# nChannel.net
KiCad netlist of a schematic drawn in EAGLE
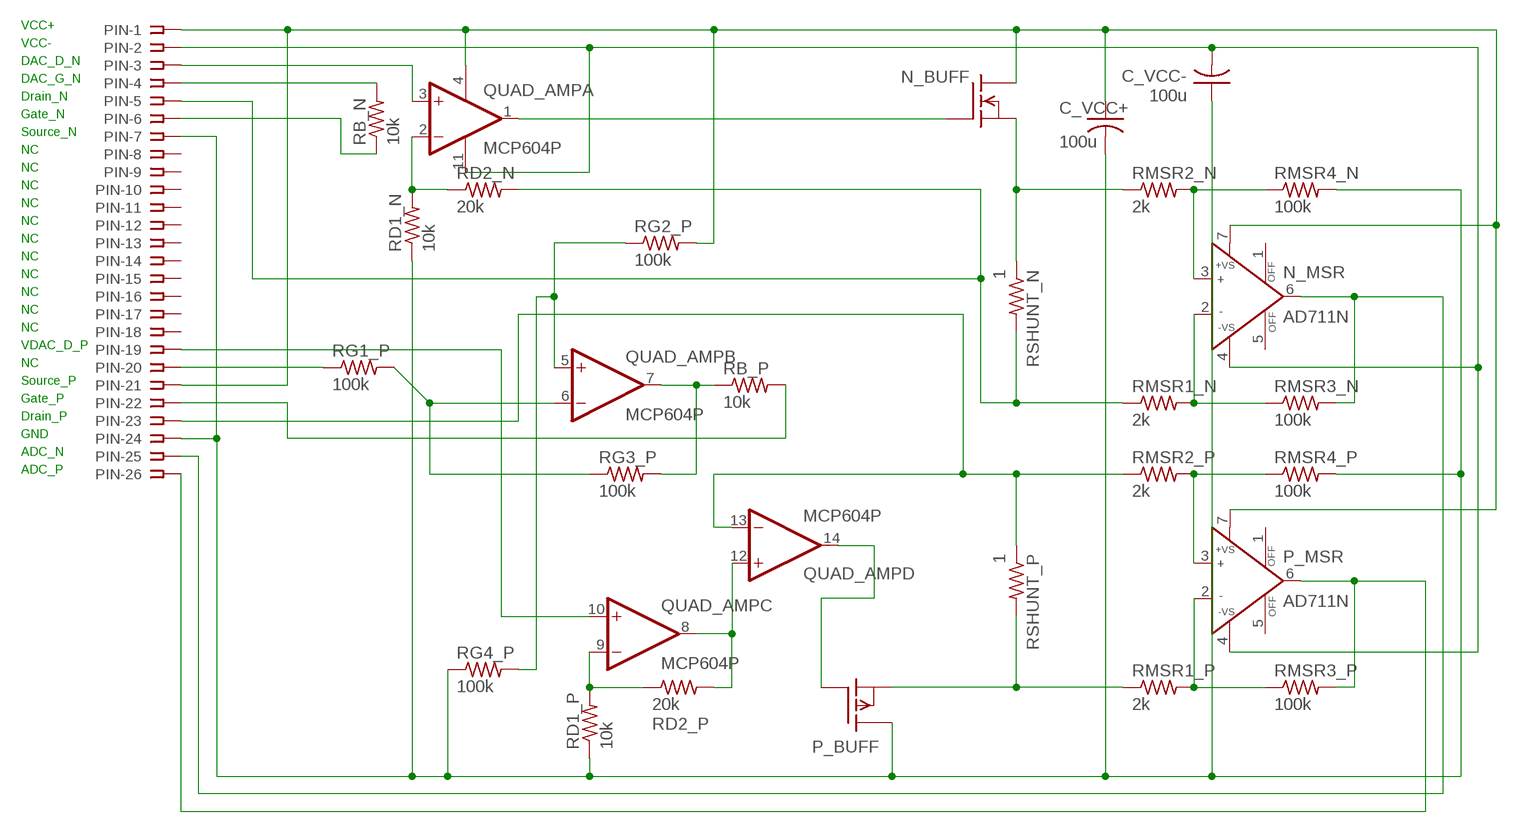
[diagram p0: schematic, sheet 1]

(export (version "E")
  (design (tool "Eeschema 10.0.6"))
  (components
    (comp (ref "C_VCC+")
      (value "100u")
      (footprint "eagle-import:C025-024X044")
      (libsource (lib "eagle-import") (part "C-US025-024X044"))
    )
    (comp (ref "C_VCC-")
      (value "100u")
      (footprint "eagle-import:C025-024X044")
      (libsource (lib "eagle-import") (part "C-US025-024X044"))
    )
    (comp (ref "N_BUFF")
      (value "BSS101")
      (footprint "eagle-import:TO92")
      (libsource (lib "eagle-import") (part "BSS101"))
    )
    (comp (ref "N_MSR")
      (value "AD711N")
      (footprint "eagle-import:DIL08")
      (fields (field (name "MPN") "AD711BQ"))
      (libsource (lib "eagle-import") (part "AD711N"))
    )
    (comp (ref "PIN")
      (value "SSW-126-02-G-S")
      (footprint "eagle-import:SSW-126-02-G-S")
      (fields (field (name "MF") "Samtec Inc."))
      (libsource (lib "eagle-import") (part "SSW-126-02-G-S"))
    )
    (comp (ref "P_BUFF")
      (value "BSS110")
      (footprint "eagle-import:TO92")
      (libsource (lib "eagle-import") (part "BSS110"))
    )
    (comp (ref "P_MSR")
      (value "AD711N")
      (footprint "eagle-import:DIL08")
      (fields (field (name "MPN") "AD711BQ"))
      (libsource (lib "eagle-import") (part "AD711N"))
    )
    (comp (ref "QUAD_AMP")
      (value "MCP604P")
      (footprint "eagle-import:DIL14")
      (libsource (lib "eagle-import") (part "MCP604P"))
    )
    (comp (ref "RB_N")
      (value "10k")
      (footprint "eagle-import:0204_5")
      (libsource (lib "eagle-import") (part "R-US_0204/5"))
    )
    (comp (ref "RB_P")
      (value "10k")
      (footprint "eagle-import:0204_5")
      (libsource (lib "eagle-import") (part "R-US_0204/5"))
    )
    (comp (ref "RD1_N")
      (value "10k")
      (footprint "eagle-import:0204_5")
      (libsource (lib "eagle-import") (part "R-US_0204/5"))
    )
    (comp (ref "RD1_P")
      (value "10k")
      (footprint "eagle-import:0204_5")
      (libsource (lib "eagle-import") (part "R-US_0204/5"))
    )
    (comp (ref "RD2_N")
      (value "20k")
      (footprint "eagle-import:0204_5")
      (libsource (lib "eagle-import") (part "R-US_0204/5"))
    )
    (comp (ref "RD2_P")
      (value "20k")
      (footprint "eagle-import:0204_5")
      (libsource (lib "eagle-import") (part "R-US_0204/5"))
    )
    (comp (ref "RG1_P")
      (value "100k")
      (footprint "eagle-import:0204_5")
      (libsource (lib "eagle-import") (part "R-US_0204/5"))
    )
    (comp (ref "RG2_P")
      (value "100k")
      (footprint "eagle-import:0204_5")
      (libsource (lib "eagle-import") (part "R-US_0204/5"))
    )
    (comp (ref "RG3_P")
      (value "100k")
      (footprint "eagle-import:0204_5")
      (libsource (lib "eagle-import") (part "R-US_0204/5"))
    )
    (comp (ref "RG4_P")
      (value "100k")
      (footprint "eagle-import:0204_5")
      (libsource (lib "eagle-import") (part "R-US_0204/5"))
    )
    (comp (ref "RMSR1_N")
      (value "2k")
      (footprint "eagle-import:0204_5")
      (libsource (lib "eagle-import") (part "R-US_0204/5"))
    )
    (comp (ref "RMSR1_P")
      (value "2k")
      (footprint "eagle-import:0204_5")
      (libsource (lib "eagle-import") (part "R-US_0204/5"))
    )
    (comp (ref "RMSR2_N")
      (value "2k")
      (footprint "eagle-import:0204_5")
      (libsource (lib "eagle-import") (part "R-US_0204/5"))
    )
    (comp (ref "RMSR2_P")
      (value "2k")
      (footprint "eagle-import:0204_5")
      (libsource (lib "eagle-import") (part "R-US_0204/5"))
    )
    (comp (ref "RMSR3_N")
      (value "100k")
      (footprint "eagle-import:0204_5")
      (libsource (lib "eagle-import") (part "R-US_0204/5"))
    )
    (comp (ref "RMSR3_P")
      (value "100k")
      (footprint "eagle-import:0204_5")
      (libsource (lib "eagle-import") (part "R-US_0204/5"))
    )
    (comp (ref "RMSR4_N")
      (value "100k")
      (footprint "eagle-import:0204_5")
      (libsource (lib "eagle-import") (part "R-US_0204/5"))
    )
    (comp (ref "RMSR4_P")
      (value "100k")
      (footprint "eagle-import:0204_5")
      (libsource (lib "eagle-import") (part "R-US_0204/5"))
    )
    (comp (ref "RSHUNT_N")
      (value "1")
      (footprint "eagle-import:0204_5")
      (fields (field (name "SPICEPREFIX") "52"))
      (libsource (lib "eagle-import") (part "R-US_0204/5"))
    )
    (comp (ref "RSHUNT_P")
      (value "1")
      (footprint "eagle-import:0204_5")
      (fields (field (name "SPICEPREFIX") "52"))
      (libsource (lib "eagle-import") (part "R-US_0204/5"))
    )
  )
  (nets
    (net (code "1") (name "Net-(N_BUFF-D)") (class "Default")
      (node (ref "C_VCC+") (pin "1") (pinfunction "1_1") (pintype "passive"))
      (node (ref "N_BUFF") (pin "3") (pinfunction "D_3") (pintype "passive"))
      (node (ref "N_MSR") (pin "7") (pinfunction "+VS_7") (pintype "input"))
      (node (ref "PIN") (pin "1") (pinfunction "1_1") (pintype "passive"))
      (node (ref "PIN") (pin "21") (pinfunction "1_21") (pintype "passive"))
      (node (ref "P_MSR") (pin "7") (pinfunction "+VS_7") (pintype "input"))
      (node (ref "QUAD_AMP") (pin "4") (pinfunction "V+_4") (pintype "power_in"))
      (node (ref "RG2_P") (pin "2") (pinfunction "2_2") (pintype "passive"))
    )
    (net (code "2") (name "Net-(N_BUFF-G)") (class "Default")
      (node (ref "N_BUFF") (pin "2") (pinfunction "G_2") (pintype "passive"))
      (node (ref "QUAD_AMP") (pin "1") (pinfunction "OUT_1") (pintype "output"))
    )
    (net (code "3") (name "Net-(N_BUFF-S)") (class "Default")
      (node (ref "N_BUFF") (pin "1") (pinfunction "S_1") (pintype "passive"))
      (node (ref "RMSR2_N") (pin "1") (pinfunction "1_1") (pintype "passive"))
      (node (ref "RSHUNT_N") (pin "1") (pinfunction "1_1") (pintype "passive"))
    )
    (net (code "4") (name "Net-(N_MSR--VS)") (class "Default")
      (node (ref "C_VCC-") (pin "2") (pinfunction "2_2") (pintype "passive"))
      (node (ref "N_MSR") (pin "4") (pinfunction "-VS_4") (pintype "input"))
      (node (ref "PIN") (pin "2") (pinfunction "1_2") (pintype "passive"))
      (node (ref "P_MSR") (pin "4") (pinfunction "-VS_4") (pintype "input"))
      (node (ref "QUAD_AMP") (pin "11") (pinfunction "V-_11") (pintype "power_in"))
    )
    (net (code "5") (name "Net-(N_MSR-IN+)") (class "Default")
      (node (ref "N_MSR") (pin "3") (pinfunction "IN+_3") (pintype "input"))
      (node (ref "RMSR2_N") (pin "2") (pinfunction "2_2") (pintype "passive"))
      (node (ref "RMSR4_N") (pin "1") (pinfunction "1_1") (pintype "passive"))
    )
    (net (code "6") (name "Net-(N_MSR-IN-)") (class "Default")
      (node (ref "N_MSR") (pin "2") (pinfunction "IN-_2") (pintype "input"))
      (node (ref "RMSR1_N") (pin "2") (pinfunction "2_2") (pintype "passive"))
      (node (ref "RMSR3_N") (pin "1") (pinfunction "1_1") (pintype "passive"))
    )
    (net (code "7") (name "Net-(N_MSR-OUT)") (class "Default")
      (node (ref "N_MSR") (pin "6") (pinfunction "OUT_6") (pintype "output"))
      (node (ref "PIN") (pin "25") (pinfunction "1_25") (pintype "passive"))
      (node (ref "RMSR3_N") (pin "2") (pinfunction "2_2") (pintype "passive"))
    )
    (net (code "8") (name "Net-(PINK-1)") (class "Default")
      (node (ref "PIN") (pin "19") (pinfunction "1_19") (pintype "passive"))
      (node (ref "QUAD_AMP") (pin "10") (pinfunction "+IN_10") (pintype "input"))
    )
    (net (code "9") (name "Net-(PINM-1)") (class "Default")
      (node (ref "PIN") (pin "20") (pinfunction "1_20") (pintype "passive"))
      (node (ref "RG1_P") (pin "1") (pinfunction "1_1") (pintype "passive"))
    )
    (net (code "10") (name "Net-(PINO-1)") (class "Default")
      (node (ref "PIN") (pin "22") (pinfunction "1_22") (pintype "passive"))
      (node (ref "RB_P") (pin "2") (pinfunction "2_2") (pintype "passive"))
    )
    (net (code "11") (name "Net-(PINP-1)") (class "Default")
      (node (ref "PIN") (pin "23") (pinfunction "1_23") (pintype "passive"))
      (node (ref "QUAD_AMP") (pin "13") (pinfunction "-IN_13") (pintype "input"))
      (node (ref "RMSR2_P") (pin "1") (pinfunction "1_1") (pintype "passive"))
      (node (ref "RSHUNT_P") (pin "1") (pinfunction "1_1") (pintype "passive"))
    )
    (net (code "12") (name "Net-(PINQ-1)") (class "Default")
      (node (ref "C_VCC+") (pin "2") (pinfunction "2_2") (pintype "passive"))
      (node (ref "C_VCC-") (pin "1") (pinfunction "1_1") (pintype "passive"))
      (node (ref "PIN") (pin "24") (pinfunction "1_24") (pintype "passive"))
      (node (ref "PIN") (pin "7") (pinfunction "1_7") (pintype "passive"))
      (node (ref "P_BUFF") (pin "3") (pinfunction "D_3") (pintype "passive"))
      (node (ref "RD1_N") (pin "1") (pinfunction "1_1") (pintype "passive"))
      (node (ref "RD1_P") (pin "1") (pinfunction "1_1") (pintype "passive"))
      (node (ref "RG4_P") (pin "1") (pinfunction "1_1") (pintype "passive"))
      (node (ref "RMSR4_N") (pin "2") (pinfunction "2_2") (pintype "passive"))
      (node (ref "RMSR4_P") (pin "2") (pinfunction "2_2") (pintype "passive"))
    )
    (net (code "13") (name "Net-(PINS-1)") (class "Default")
      (node (ref "PIN") (pin "26") (pinfunction "1_26") (pintype "passive"))
      (node (ref "P_MSR") (pin "6") (pinfunction "OUT_6") (pintype "output"))
      (node (ref "RMSR3_P") (pin "2") (pinfunction "2_2") (pintype "passive"))
    )
    (net (code "14") (name "Net-(PINT-1)") (class "Default")
      (node (ref "PIN") (pin "3") (pinfunction "1_3") (pintype "passive"))
      (node (ref "QUAD_AMP") (pin "3") (pinfunction "+IN_3") (pintype "input"))
    )
    (net (code "15") (name "Net-(PINU-1)") (class "Default")
      (node (ref "PIN") (pin "4") (pinfunction "1_4") (pintype "passive"))
      (node (ref "RB_N") (pin "2") (pinfunction "2_2") (pintype "passive"))
    )
    (net (code "16") (name "Net-(PINV-1)") (class "Default")
      (node (ref "PIN") (pin "5") (pinfunction "1_5") (pintype "passive"))
      (node (ref "RD2_N") (pin "2") (pinfunction "2_2") (pintype "passive"))
      (node (ref "RMSR1_N") (pin "1") (pinfunction "1_1") (pintype "passive"))
      (node (ref "RSHUNT_N") (pin "2") (pinfunction "2_2") (pintype "passive"))
    )
    (net (code "17") (name "Net-(PINW-1)") (class "Default")
      (node (ref "PIN") (pin "6") (pinfunction "1_6") (pintype "passive"))
      (node (ref "RB_N") (pin "1") (pinfunction "1_1") (pintype "passive"))
    )
    (net (code "18") (name "Net-(P_BUFF-G)") (class "Default")
      (node (ref "P_BUFF") (pin "2") (pinfunction "G_2") (pintype "passive"))
      (node (ref "QUAD_AMP") (pin "14") (pinfunction "OUT_14") (pintype "output"))
    )
    (net (code "19") (name "Net-(P_BUFF-S)") (class "Default")
      (node (ref "P_BUFF") (pin "1") (pinfunction "S_1") (pintype "passive"))
      (node (ref "RMSR1_P") (pin "1") (pinfunction "1_1") (pintype "passive"))
      (node (ref "RSHUNT_P") (pin "2") (pinfunction "2_2") (pintype "passive"))
    )
    (net (code "20") (name "Net-(P_MSR-IN+)") (class "Default")
      (node (ref "P_MSR") (pin "3") (pinfunction "IN+_3") (pintype "input"))
      (node (ref "RMSR2_P") (pin "2") (pinfunction "2_2") (pintype "passive"))
      (node (ref "RMSR4_P") (pin "1") (pinfunction "1_1") (pintype "passive"))
    )
    (net (code "21") (name "Net-(P_MSR-IN-)") (class "Default")
      (node (ref "P_MSR") (pin "2") (pinfunction "IN-_2") (pintype "input"))
      (node (ref "RMSR1_P") (pin "2") (pinfunction "2_2") (pintype "passive"))
      (node (ref "RMSR3_P") (pin "1") (pinfunction "1_1") (pintype "passive"))
    )
    (net (code "22") (name "Net-(QUAD_AMPA--IN)") (class "Default")
      (node (ref "QUAD_AMP") (pin "2") (pinfunction "-IN_2") (pintype "input"))
      (node (ref "RD1_N") (pin "2") (pinfunction "2_2") (pintype "passive"))
      (node (ref "RD2_N") (pin "1") (pinfunction "1_1") (pintype "passive"))
    )
    (net (code "23") (name "Net-(QUAD_AMPB-+IN)") (class "Default")
      (node (ref "QUAD_AMP") (pin "5") (pinfunction "+IN_5") (pintype "input"))
      (node (ref "RG2_P") (pin "1") (pinfunction "1_1") (pintype "passive"))
      (node (ref "RG4_P") (pin "2") (pinfunction "2_2") (pintype "passive"))
    )
    (net (code "24") (name "Net-(QUAD_AMPB--IN)") (class "Default")
      (node (ref "QUAD_AMP") (pin "6") (pinfunction "-IN_6") (pintype "input"))
      (node (ref "RG1_P") (pin "2") (pinfunction "2_2") (pintype "passive"))
      (node (ref "RG3_P") (pin "1") (pinfunction "1_1") (pintype "passive"))
    )
    (net (code "25") (name "Net-(QUAD_AMPB-OUT)") (class "Default")
      (node (ref "QUAD_AMP") (pin "7") (pinfunction "OUT_7") (pintype "output"))
      (node (ref "RB_P") (pin "1") (pinfunction "1_1") (pintype "passive"))
      (node (ref "RG3_P") (pin "2") (pinfunction "2_2") (pintype "passive"))
    )
    (net (code "26") (name "Net-(QUAD_AMPC--IN)") (class "Default")
      (node (ref "QUAD_AMP") (pin "9") (pinfunction "-IN_9") (pintype "input"))
      (node (ref "RD1_P") (pin "2") (pinfunction "2_2") (pintype "passive"))
      (node (ref "RD2_P") (pin "1") (pinfunction "1_1") (pintype "passive"))
    )
    (net (code "27") (name "Net-(QUAD_AMPC-OUT)") (class "Default")
      (node (ref "QUAD_AMP") (pin "12") (pinfunction "+IN_12") (pintype "input"))
      (node (ref "QUAD_AMP") (pin "8") (pinfunction "OUT_8") (pintype "output"))
      (node (ref "RD2_P") (pin "2") (pinfunction "2_2") (pintype "passive"))
    )
    (net (code "28") (name "unconnected-(N_MSR-OFF-Pad1)") (class "Default")
      (node (ref "N_MSR") (pin "1") (pinfunction "OFF_1") (pintype "passive"))
    )
    (net (code "29") (name "unconnected-(N_MSR-OFF-Pad5)") (class "Default")
      (node (ref "N_MSR") (pin "5") (pinfunction "OFF_5") (pintype "passive"))
    )
    (net (code "30") (name "unconnected-(PINB-1-Pad10)") (class "Default")
      (node (ref "PIN") (pin "10") (pinfunction "1_10") (pintype "passive"))
    )
    (net (code "31") (name "unconnected-(PINC-1-Pad11)") (class "Default")
      (node (ref "PIN") (pin "11") (pinfunction "1_11") (pintype "passive"))
    )
    (net (code "32") (name "unconnected-(PIND-1-Pad12)") (class "Default")
      (node (ref "PIN") (pin "12") (pinfunction "1_12") (pintype "passive"))
    )
    (net (code "33") (name "unconnected-(PINE-1-Pad13)") (class "Default")
      (node (ref "PIN") (pin "13") (pinfunction "1_13") (pintype "passive"))
    )
    (net (code "34") (name "unconnected-(PINF-1-Pad14)") (class "Default")
      (node (ref "PIN") (pin "14") (pinfunction "1_14") (pintype "passive"))
    )
    (net (code "35") (name "unconnected-(PING-1-Pad15)") (class "Default")
      (node (ref "PIN") (pin "15") (pinfunction "1_15") (pintype "passive"))
    )
    (net (code "36") (name "unconnected-(PINH-1-Pad16)") (class "Default")
      (node (ref "PIN") (pin "16") (pinfunction "1_16") (pintype "passive"))
    )
    (net (code "37") (name "unconnected-(PINI-1-Pad17)") (class "Default")
      (node (ref "PIN") (pin "17") (pinfunction "1_17") (pintype "passive"))
    )
    (net (code "38") (name "unconnected-(PINJ-1-Pad18)") (class "Default")
      (node (ref "PIN") (pin "18") (pinfunction "1_18") (pintype "passive"))
    )
    (net (code "39") (name "unconnected-(PINY-1-Pad8)") (class "Default")
      (node (ref "PIN") (pin "8") (pinfunction "1_8") (pintype "passive"))
    )
    (net (code "40") (name "unconnected-(PINZ-1-Pad9)") (class "Default")
      (node (ref "PIN") (pin "9") (pinfunction "1_9") (pintype "passive"))
    )
    (net (code "41") (name "unconnected-(P_MSR-OFF-Pad1)") (class "Default")
      (node (ref "P_MSR") (pin "1") (pinfunction "OFF_1") (pintype "passive"))
    )
    (net (code "42") (name "unconnected-(P_MSR-OFF-Pad5)") (class "Default")
      (node (ref "P_MSR") (pin "5") (pinfunction "OFF_5") (pintype "passive"))
    )
  )
)
